# Pulsadores.net
KiCad netlist of a schematic drawn in Altium Designer
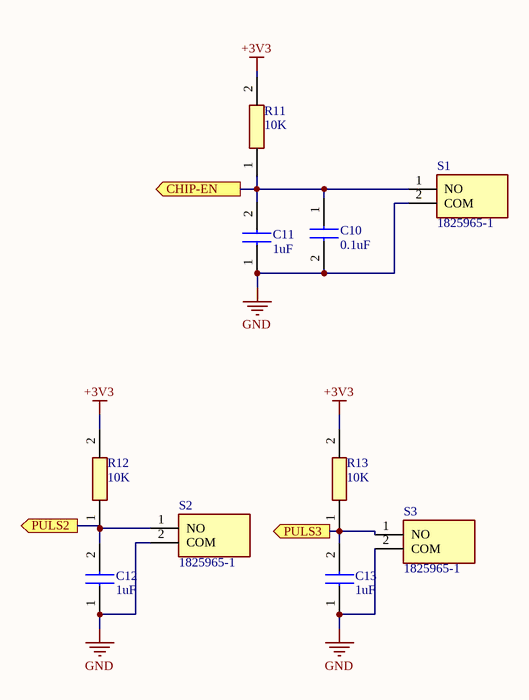
[diagram p0: Pulsadores.SchDoc]

(export (version "E")
  (design (tool "Eeschema 10.0.6"))
  (components
    (comp (ref "C10")
      (value "0.1uF")
      (footprint "SamacSys:CAPC3216X100N")
      (description "100NFX50V X7R 10% CER.MULT. SMD 1206")
      (fields
        (field (name "MANUFACTURER_PART_NUMBER") "CL31B104KBCNNNC")
        (field (name "MOUSER PART NUMBER") "187-CL31B104KBCNNNC")
      )
      (libsource (lib "*") (part "CL31B104KBCNNNC"))
    )
    (comp (ref "C11")
      (value "1uF")
      (footprint "SamacSys:CAPC3216X100N")
      (description "100NFX50V X7R 10% CER.MULT. SMD 1206")
      (fields
        (field (name "MANUFACTURER_PART_NUMBER") "CL31B104KBCNNNC")
        (field (name "MOUSER PART NUMBER") "187-CL31B104KBCNNNC")
      )
      (libsource (lib "*") (part "CL31B104KBCNNNC"))
    )
    (comp (ref "C12")
      (value "1uF")
      (footprint "SamacSys:CAPC3216X100N")
      (description "100NFX50V X7R 10% CER.MULT. SMD 1206")
      (fields
        (field (name "MANUFACTURER_PART_NUMBER") "CL31B104KBCNNNC")
        (field (name "MOUSER PART NUMBER") "187-CL31B104KBCNNNC")
      )
      (libsource (lib "*") (part "CL31B104KBCNNNC"))
    )
    (comp (ref "C13")
      (value "1uF")
      (footprint "SamacSys:CAPC3216X100N")
      (description "100NFX50V X7R 10% CER.MULT. SMD 1206")
      (fields
        (field (name "MANUFACTURER_PART_NUMBER") "CL31B104KBCNNNC")
        (field (name "MOUSER PART NUMBER") "187-CL31B104KBCNNNC")
      )
      (libsource (lib "*") (part "CL31B104KBCNNNC"))
    )
    (comp (ref "R11")
      (value "10K")
      (footprint "SamacSys:RESC3216X75N")
      (description "Resistor")
      (fields
        (field (name "MANUFACTURER_PART_NUMBER") "CR1206-F/-2R00ELF")
        (field (name "MOUSER PART NUMBER") "652-CR1206-F/2R00ELF")
      )
      (libsource (lib "*") (part "CR1206-F_-2R00ELF"))
    )
    (comp (ref "R12")
      (value "10K")
      (footprint "SamacSys:RESC3216X75N")
      (description "Resistor")
      (fields
        (field (name "MANUFACTURER_PART_NUMBER") "CR1206-F/-2R00ELF")
        (field (name "MOUSER PART NUMBER") "652-CR1206-F/2R00ELF")
      )
      (libsource (lib "*") (part "CR1206-F_-2R00ELF"))
    )
    (comp (ref "R13")
      (value "10K")
      (footprint "SamacSys:RESC3216X75N")
      (description "Resistor")
      (fields
        (field (name "MANUFACTURER_PART_NUMBER") "CR1206-F/-2R00ELF")
        (field (name "MOUSER PART NUMBER") "652-CR1206-F/2R00ELF")
      )
      (libsource (lib "*") (part "CR1206-F_-2R00ELF"))
    )
    (comp (ref "S1")
      (value "1825965-1")
      (footprint "Libreria:TAC-SWITCH 2CONT. 3,5X6MM")
      (description "Switch")
      (libsource (lib "*") (part "1825965-1"))
    )
    (comp (ref "S2")
      (value "1825965-1")
      (footprint "Libreria:TAC-SWITCH 2CONT. 3,5X6MM")
      (description "Switch")
      (libsource (lib "*") (part "1825965-1"))
    )
    (comp (ref "S3")
      (value "1825965-1")
      (footprint "Libreria:TAC-SWITCH 2CONT. 3,5X6MM")
      (description "Switch")
      (libsource (lib "*") (part "1825965-1"))
    )
  )
  (nets
    (net (code "1") (name "+3V3") (class "Default")
      (node (ref "R11") (pin "2") (pinfunction "2_2") (pintype "passive"))
      (node (ref "R12") (pin "2") (pinfunction "2_2") (pintype "passive"))
      (node (ref "R13") (pin "2") (pinfunction "2_2") (pintype "passive"))
    )
    (net (code "2") (name "/CHIP-EN") (class "Default")
      (node (ref "C10") (pin "1") (pinfunction "1_1") (pintype "passive"))
      (node (ref "C11") (pin "2") (pinfunction "2_2") (pintype "passive"))
      (node (ref "R11") (pin "1") (pinfunction "1_1") (pintype "passive"))
      (node (ref "S1") (pin "1") (pinfunction "NO_1") (pintype "passive"))
    )
    (net (code "3") (name "/PULS2") (class "Default")
      (node (ref "C12") (pin "2") (pinfunction "2_2") (pintype "passive"))
      (node (ref "R12") (pin "1") (pinfunction "1_1") (pintype "passive"))
      (node (ref "S2") (pin "1") (pinfunction "NO_1") (pintype "passive"))
    )
    (net (code "4") (name "/PULS3") (class "Default")
      (node (ref "C13") (pin "2") (pinfunction "2_2") (pintype "passive"))
      (node (ref "R13") (pin "1") (pinfunction "1_1") (pintype "passive"))
      (node (ref "S3") (pin "1") (pinfunction "NO_1") (pintype "passive"))
    )
    (net (code "5") (name "GND") (class "Default")
      (node (ref "C10") (pin "2") (pinfunction "2_2") (pintype "passive"))
      (node (ref "C11") (pin "1") (pinfunction "1_1") (pintype "passive"))
      (node (ref "C12") (pin "1") (pinfunction "1_1") (pintype "passive"))
      (node (ref "C13") (pin "1") (pinfunction "1_1") (pintype "passive"))
      (node (ref "S1") (pin "2") (pinfunction "COM_2") (pintype "passive"))
      (node (ref "S2") (pin "2") (pinfunction "COM_2") (pintype "passive"))
      (node (ref "S3") (pin "2") (pinfunction "COM_2") (pintype "passive"))
    )
  )
)
